# AFE_B.net
KiCad netlist of a schematic drawn in Altium Designer
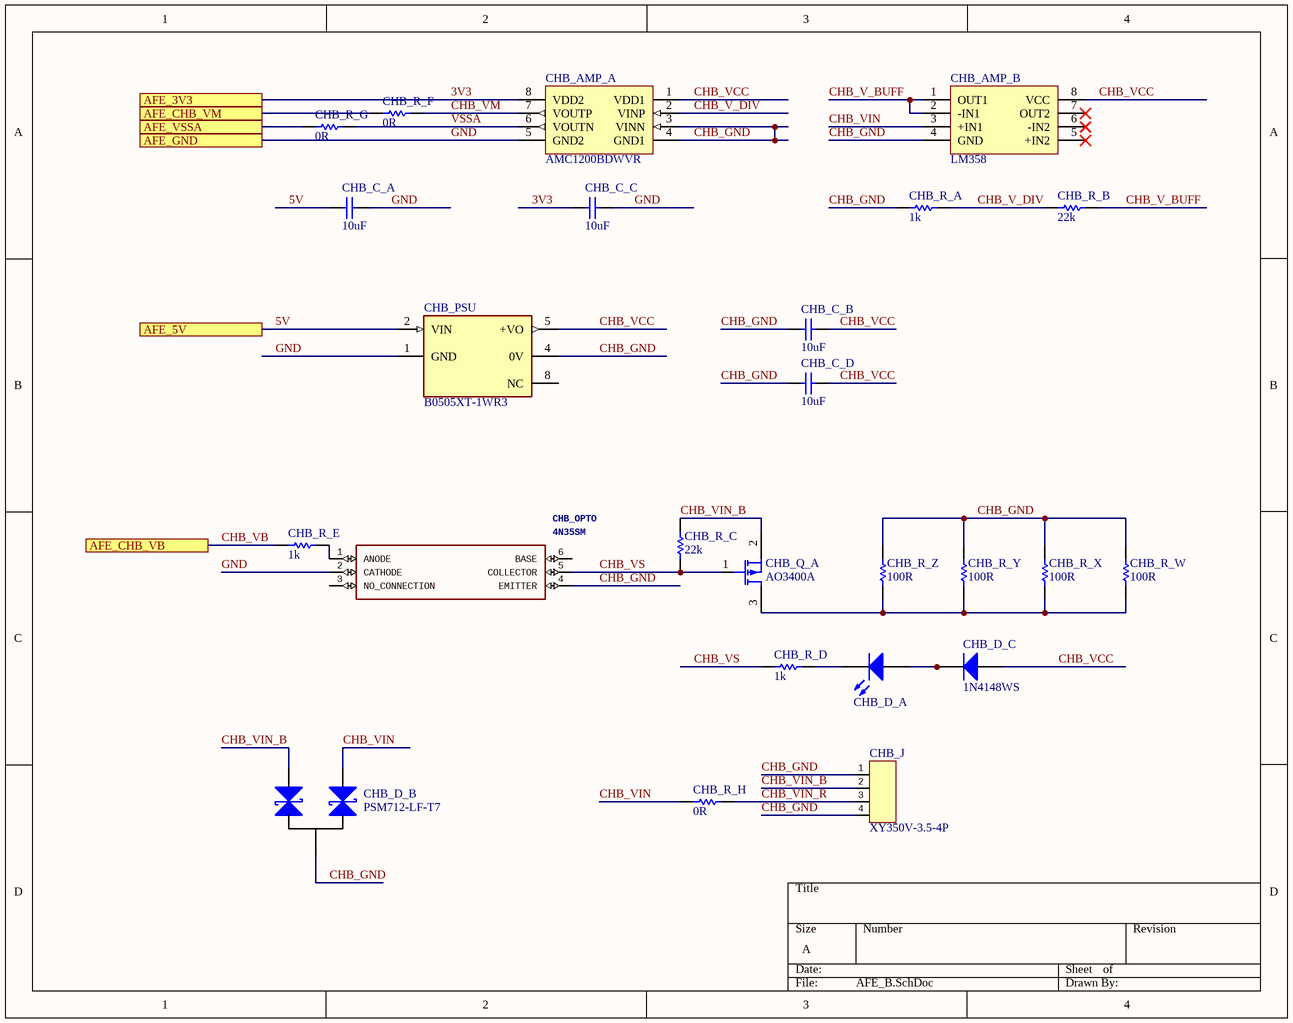
[diagram p0: AFE_B.SchDoc]

(export (version "E")
  (design (tool "Eeschema 10.0.6"))
  (components
    (comp (ref "CHB_AMP_A")
      (value "AMC1200BDWVR")
      (footprint "FOOTPRINTS:SOIC-8-P1.27-W7.5")
      (description "U - IC - 100KHz ISOLATION AMPLIFIER")
      (fields (field (name "LCSC PART #") "C79905"))
      (libsource (lib "JLC_PCB") (part "AMC1200BDWVR"))
    )
    (comp (ref "CHB_AMP_B")
      (value "LM358")
      (footprint "FOOTPRINTS:SOIC-8-P1.27-W3.5")
      (description "U - IC - OP AMP (DUAL)")
      (fields (field (name "LCSC PART #") "C63813"))
      (libsource (lib "JLC_PCB") (part "LMV358IDR"))
    )
    (comp (ref "CHB_C_A")
      (value "10uF")
      (footprint "C_0603")
      (description "C - CAPACITOR - MLCC - 10uF - 25V - 0603")
      (fields (field (name "LCSC PART #") "C96446") (field (name "Comment") "CL10A106MA8NRNC"))
      (libsource (lib "JLC_PCB") (part "CL10A106MA8NRNC"))
    )
    (comp (ref "CHB_C_B")
      (value "10uF")
      (footprint "C_0603")
      (description "C - CAPACITOR - MLCC - 10uF - 25V - 0603")
      (fields (field (name "LCSC PART #") "C96446") (field (name "Comment") "CL10A106MA8NRNC"))
      (libsource (lib "JLC_PCB") (part "CL10A106MA8NRNC"))
    )
    (comp (ref "CHB_C_C")
      (value "10uF")
      (footprint "C_0603")
      (description "C - CAPACITOR - MLCC - 10uF - 25V - 0603")
      (fields (field (name "LCSC PART #") "C96446") (field (name "Comment") "CL10A106MA8NRNC"))
      (libsource (lib "JLC_PCB") (part "CL10A106MA8NRNC"))
    )
    (comp (ref "CHB_C_D")
      (value "10uF")
      (footprint "C_0603")
      (description "C - CAPACITOR - MLCC - 10uF - 25V - 0603")
      (fields (field (name "LCSC PART #") "C96446") (field (name "Comment") "CL10A106MA8NRNC"))
      (libsource (lib "JLC_PCB") (part "CL10A106MA8NRNC"))
    )
    (comp (ref "CHB_D_A")
      (value "KT-0603R")
      (footprint "D_0603")
      (description "D - LED - 0603 - Red")
      (fields (field (name "LCSC PART #") "C2286"))
      (libsource (lib "JLC_PCB") (part "KT-0603R"))
    )
    (comp (ref "CHB_D_B")
      (value "PSM712-LF-T7")
      (footprint "TO-236AB")
      (description "D - DIODE - TVS x2 - 7.2V")
      (fields (field (name "LCSC PART #") "C32677"))
      (libsource (lib "JLC_PCB") (part "PSM712-LF-T7"))
    )
    (comp (ref "CHB_D_C")
      (value "1N4148WS")
      (footprint "SOD-323")
      (description "D - DIODE - FAST TRR - 100V - 150mA - 4ns")
      (fields (field (name "LCSC PART #") "C2128"))
      (libsource (lib "JLC_PCB") (part "1N4148WS"))
    )
    (comp (ref "CHB_J")
      (value "XY350V-3.5-4P")
      (footprint "XY350V-3.5-4P")
      (description "J - JACK - TERMINAL - 4P - RIGHT - MALE")
      (fields (field (name "LCSC PART #") "C557656"))
      (libsource (lib "JLC_PCB") (part "XY350V-3.5-4P"))
    )
    (comp (ref "CHB_OPTO")
      (value "4N35SM")
      (footprint "SOT254P916X508-6N")
      (description "Q - OPTOCOUPLER - 4170 V - 100% CTR")
      (fields (field (name "LCSC PART #") "C258228"))
      (libsource (lib "JLC_PCB") (part "4N35SM"))
    )
    (comp (ref "CHB_PSU")
      (value "B0505XT-1WR3")
      (footprint "CONV_B0512XT-1WR3")
      (description "T - Isolated Module DC DC Converter 5 -> 5V 200mA - DIP")
      (fields (field (name "LCSC PART #") "C19188495") (field (name "MF") "EVISUN"))
      (libsource (lib "JLC_PCB") (part "B0505XT-1WR3"))
    )
    (comp (ref "CHB_Q_A")
      (value "AO3400A")
      (footprint "TO-236AB")
      (description "Q - TRANSISTOR - MOSFET (P) - 20V - 3.4A - 0.26 Ohm")
      (fields (field (name "LCSC PART #") "C20917"))
      (libsource (lib "JLC_PCB") (part "AO3400A"))
    )
    (comp (ref "CHB_R_A")
      (value "1k")
      (footprint "R_0603")
      (description "R - RESISTOR - SMD - 1k - 1% - 0603")
      (fields (field (name "LCSC PART #") "C21190") (field (name "Comment") "0603WAF1001T5E"))
      (libsource (lib "JLC_PCB") (part "0603WAF1001T5E"))
    )
    (comp (ref "CHB_R_B")
      (value "22k")
      (footprint "R_0603")
      (description "R - RESISTOR - SMD - 22k - 1% - 0603")
      (fields (field (name "LCSC PART #") "C31850") (field (name "Comment") "0603WAF2202T5E"))
      (libsource (lib "JLC_PCB") (part "0603WAF2202T5E"))
    )
    (comp (ref "CHB_R_C")
      (value "22k")
      (footprint "R_0603")
      (description "R - RESISTOR - SMD - 22k - 1% - 0603")
      (fields (field (name "LCSC PART #") "C31850") (field (name "Comment") "0603WAF2202T5E"))
      (libsource (lib "JLC_PCB") (part "0603WAF2202T5E"))
    )
    (comp (ref "CHB_R_D")
      (value "1k")
      (footprint "R_0603")
      (description "R - RESISTOR - SMD - 1k - 1% - 0603")
      (fields (field (name "LCSC PART #") "C21190") (field (name "Comment") "0603WAF1001T5E"))
      (libsource (lib "JLC_PCB") (part "0603WAF1001T5E"))
    )
    (comp (ref "CHB_R_E")
      (value "1k")
      (footprint "R_0603")
      (description "R - RESISTOR - SMD - 1k - 1% - 0603")
      (fields (field (name "LCSC PART #") "C21190") (field (name "Comment") "0603WAF1001T5E"))
      (libsource (lib "JLC_PCB") (part "0603WAF1001T5E"))
    )
    (comp (ref "CHB_R_F")
      (value "0R")
      (footprint "R_0603")
      (description "R - RESISTOR - SMD - 0R - 1% - 0603")
      (fields (field (name "LCSC PART #") "C21189") (field (name "Comment") "0603WAF0000T5E"))
      (libsource (lib "JLC_PCB") (part "0603WAF0000T5E"))
    )
    (comp (ref "CHB_R_G")
      (value "0R")
      (footprint "R_0603")
      (description "R - RESISTOR - SMD - 0R - 1% - 0603")
      (fields (field (name "LCSC PART #") "C21189") (field (name "Comment") "0603WAF0000T5E"))
      (libsource (lib "JLC_PCB") (part "0603WAF0000T5E"))
    )
    (comp (ref "CHB_R_H")
      (value "0R")
      (footprint "R_0603")
      (description "R - RESISTOR - SMD - 0R - 1% - 0603")
      (fields (field (name "LCSC PART #") "C21189") (field (name "Comment") "0603WAF0000T5E"))
      (libsource (lib "JLC_PCB") (part "0603WAF0000T5E"))
    )
    (comp (ref "CHB_R_W")
      (value "100R")
      (footprint "R_1206")
      (description "R - RESISTOR - SMD - 100R - 1% - 1206")
      (fields (field (name "LCSC PART #") "C17901") (field (name "Comment") "1206W4F1000T5E"))
      (libsource (lib "JLC_PCB") (part "1206W4F1000T5E"))
    )
    (comp (ref "CHB_R_X")
      (value "100R")
      (footprint "R_1206")
      (description "R - RESISTOR - SMD - 100R - 1% - 1206")
      (fields (field (name "LCSC PART #") "C17901") (field (name "Comment") "1206W4F1000T5E"))
      (libsource (lib "JLC_PCB") (part "1206W4F1000T5E"))
    )
    (comp (ref "CHB_R_Y")
      (value "100R")
      (footprint "R_1206")
      (description "R - RESISTOR - SMD - 100R - 1% - 1206")
      (fields (field (name "LCSC PART #") "C17901") (field (name "Comment") "1206W4F1000T5E"))
      (libsource (lib "JLC_PCB") (part "1206W4F1000T5E"))
    )
    (comp (ref "CHB_R_Z")
      (value "100R")
      (footprint "R_1206")
      (description "R - RESISTOR - SMD - 100R - 1% - 1206")
      (fields (field (name "LCSC PART #") "C17901") (field (name "Comment") "1206W4F1000T5E"))
      (libsource (lib "JLC_PCB") (part "1206W4F1000T5E"))
    )
  )
  (nets
    (net (code "1") (name "/3V3") (class "Default")
      (node (ref "CHB_AMP_A") (pin "8") (pinfunction "VDD2_8") (pintype "passive"))
      (node (ref "CHB_C_C") (pin "2") (pinfunction "2_2") (pintype "passive"))
    )
    (net (code "2") (name "/5V") (class "Default")
      (node (ref "CHB_C_A") (pin "2") (pinfunction "2_2") (pintype "passive"))
      (node (ref "CHB_PSU") (pin "2") (pinfunction "VIN_2") (pintype "input"))
    )
    (net (code "3") (name "/AFE_CHB_VM") (class "Default")
      (node (ref "CHB_R_F") (pin "1") (pinfunction "1_1") (pintype "passive"))
    )
    (net (code "4") (name "/AFE_VSSA") (class "Default")
      (node (ref "CHB_R_G") (pin "1") (pinfunction "1_1") (pintype "passive"))
    )
    (net (code "5") (name "/CHB_GND") (class "Default")
      (node (ref "CHB_AMP_A") (pin "3") (pinfunction "VINN_3") (pintype "input"))
      (node (ref "CHB_AMP_A") (pin "4") (pinfunction "GND1_4") (pintype "power_in"))
      (node (ref "CHB_AMP_B") (pin "4") (pinfunction "GND_4") (pintype "passive"))
      (node (ref "CHB_C_B") (pin "2") (pinfunction "2_2") (pintype "passive"))
      (node (ref "CHB_C_D") (pin "2") (pinfunction "2_2") (pintype "passive"))
      (node (ref "CHB_D_B") (pin "3") (pinfunction "A_3") (pintype "passive"))
      (node (ref "CHB_J") (pin "1") (pinfunction "1_1") (pintype "passive"))
      (node (ref "CHB_J") (pin "4") (pinfunction "4_4") (pintype "passive"))
      (node (ref "CHB_OPTO") (pin "4") (pinfunction "EMITTER_4") (pintype "bidirectional"))
      (node (ref "CHB_PSU") (pin "4") (pinfunction "0V_4") (pintype "passive"))
      (node (ref "CHB_R_A") (pin "1") (pinfunction "1_1") (pintype "passive"))
      (node (ref "CHB_R_W") (pin "1") (pinfunction "1_1") (pintype "passive"))
      (node (ref "CHB_R_X") (pin "1") (pinfunction "1_1") (pintype "passive"))
      (node (ref "CHB_R_Y") (pin "1") (pinfunction "1_1") (pintype "passive"))
      (node (ref "CHB_R_Z") (pin "1") (pinfunction "1_1") (pintype "passive"))
    )
    (net (code "6") (name "/CHB_VB") (class "Default")
      (node (ref "CHB_R_E") (pin "1") (pinfunction "1_1") (pintype "passive"))
    )
    (net (code "7") (name "/CHB_VCC") (class "Default")
      (node (ref "CHB_AMP_A") (pin "1") (pinfunction "VDD1_1") (pintype "passive"))
      (node (ref "CHB_AMP_B") (pin "8") (pinfunction "VCC_8") (pintype "passive"))
      (node (ref "CHB_C_B") (pin "1") (pinfunction "1_1") (pintype "passive"))
      (node (ref "CHB_C_D") (pin "1") (pinfunction "1_1") (pintype "passive"))
      (node (ref "CHB_D_C") (pin "2") (pinfunction "A_2") (pintype "passive"))
      (node (ref "CHB_PSU") (pin "5") (pinfunction "+VO_5") (pintype "output"))
    )
    (net (code "8") (name "/CHB_VIN") (class "Default")
      (node (ref "CHB_AMP_B") (pin "3") (pinfunction "+IN1_3") (pintype "passive"))
      (node (ref "CHB_D_B") (pin "2") (pinfunction "K_2") (pintype "passive"))
      (node (ref "CHB_R_H") (pin "1") (pinfunction "1_1") (pintype "passive"))
    )
    (net (code "9") (name "/CHB_VIN_B") (class "Default")
      (node (ref "CHB_D_B") (pin "1") (pinfunction "K_1") (pintype "passive"))
      (node (ref "CHB_J") (pin "2") (pinfunction "2_2") (pintype "passive"))
      (node (ref "CHB_Q_A") (pin "2") (pinfunction "S_2") (pintype "passive"))
      (node (ref "CHB_R_C") (pin "2") (pinfunction "2_2") (pintype "passive"))
    )
    (net (code "10") (name "/CHB_VIN_R") (class "Default")
      (node (ref "CHB_J") (pin "3") (pinfunction "3_3") (pintype "passive"))
      (node (ref "CHB_R_H") (pin "2") (pinfunction "2_2") (pintype "passive"))
    )
    (net (code "11") (name "/CHB_VM") (class "Default")
      (node (ref "CHB_AMP_A") (pin "7") (pinfunction "VOUTP_7") (pintype "output"))
      (node (ref "CHB_R_F") (pin "2") (pinfunction "2_2") (pintype "passive"))
    )
    (net (code "12") (name "/CHB_VS") (class "Default")
      (node (ref "CHB_OPTO") (pin "5") (pinfunction "COLLECTOR_5") (pintype "bidirectional"))
      (node (ref "CHB_Q_A") (pin "1") (pinfunction "G_1") (pintype "passive"))
      (node (ref "CHB_R_C") (pin "1") (pinfunction "1_1") (pintype "passive"))
      (node (ref "CHB_R_D") (pin "1") (pinfunction "1_1") (pintype "passive"))
    )
    (net (code "13") (name "/CHB_V_BUFF") (class "Default")
      (node (ref "CHB_AMP_B") (pin "1") (pinfunction "OUT1_1") (pintype "passive"))
      (node (ref "CHB_AMP_B") (pin "2") (pinfunction "-IN1_2") (pintype "passive"))
      (node (ref "CHB_R_B") (pin "2") (pinfunction "2_2") (pintype "passive"))
    )
    (net (code "14") (name "/CHB_V_DIV") (class "Default")
      (node (ref "CHB_AMP_A") (pin "2") (pinfunction "VINP_2") (pintype "input"))
      (node (ref "CHB_R_A") (pin "2") (pinfunction "2_2") (pintype "passive"))
      (node (ref "CHB_R_B") (pin "1") (pinfunction "1_1") (pintype "passive"))
    )
    (net (code "15") (name "/GND") (class "Default")
      (node (ref "CHB_AMP_A") (pin "5") (pinfunction "GND2_5") (pintype "power_in"))
      (node (ref "CHB_C_A") (pin "1") (pinfunction "1_1") (pintype "passive"))
      (node (ref "CHB_C_C") (pin "1") (pinfunction "1_1") (pintype "passive"))
      (node (ref "CHB_OPTO") (pin "2") (pinfunction "CATHODE_2") (pintype "bidirectional"))
      (node (ref "CHB_PSU") (pin "1") (pinfunction "GND_1") (pintype "power_in"))
    )
    (net (code "16") (name "/VSSA") (class "Default")
      (node (ref "CHB_AMP_A") (pin "6") (pinfunction "VOUTN_6") (pintype "output"))
      (node (ref "CHB_R_G") (pin "2") (pinfunction "2_2") (pintype "passive"))
    )
    (net (code "17") (name "Net-(CHB_D_A-A)") (class "Default")
      (node (ref "CHB_D_A") (pin "2") (pinfunction "A_2") (pintype "passive"))
      (node (ref "CHB_D_C") (pin "1") (pinfunction "K_1") (pintype "passive"))
    )
    (net (code "18") (name "Net-(CHB_D_A-K)") (class "Default")
      (node (ref "CHB_D_A") (pin "1") (pinfunction "K_1") (pintype "passive"))
      (node (ref "CHB_R_D") (pin "2") (pinfunction "2_2") (pintype "passive"))
    )
    (net (code "19") (name "Net-(CHB_OPTO-ANODE)") (class "Default")
      (node (ref "CHB_OPTO") (pin "1") (pinfunction "ANODE_1") (pintype "bidirectional"))
      (node (ref "CHB_R_E") (pin "2") (pinfunction "2_2") (pintype "passive"))
    )
    (net (code "20") (name "Net-(CHB_Q_A-D)") (class "Default")
      (node (ref "CHB_Q_A") (pin "3") (pinfunction "D_3") (pintype "passive"))
      (node (ref "CHB_R_W") (pin "2") (pinfunction "2_2") (pintype "passive"))
      (node (ref "CHB_R_X") (pin "2") (pinfunction "2_2") (pintype "passive"))
      (node (ref "CHB_R_Y") (pin "2") (pinfunction "2_2") (pintype "passive"))
      (node (ref "CHB_R_Z") (pin "2") (pinfunction "2_2") (pintype "passive"))
    )
    (net (code "21") (name "unconnected-(CHB_AMP_B-+IN2-Pad5)") (class "Default")
      (node (ref "CHB_AMP_B") (pin "5") (pinfunction "+IN2_5") (pintype "passive+no_connect"))
    )
    (net (code "22") (name "unconnected-(CHB_AMP_B--IN2-Pad6)") (class "Default")
      (node (ref "CHB_AMP_B") (pin "6") (pinfunction "-IN2_6") (pintype "passive+no_connect"))
    )
    (net (code "23") (name "unconnected-(CHB_AMP_B-OUT2-Pad7)") (class "Default")
      (node (ref "CHB_AMP_B") (pin "7") (pinfunction "OUT2_7") (pintype "passive+no_connect"))
    )
    (net (code "24") (name "unconnected-(CHB_OPTO-BASE-Pad6)") (class "Default")
      (node (ref "CHB_OPTO") (pin "6") (pinfunction "BASE_6") (pintype "bidirectional"))
    )
    (net (code "25") (name "unconnected-(CHB_OPTO-NO_CONNECTION-Pad3)") (class "Default")
      (node (ref "CHB_OPTO") (pin "3") (pinfunction "NO_CONNECTION_3") (pintype "bidirectional"))
    )
    (net (code "26") (name "unconnected-(CHB_PSU-NC-Pad8)") (class "Default")
      (node (ref "CHB_PSU") (pin "8") (pinfunction "NC_8") (pintype "passive"))
    )
  )
)
